# ESP32.net
KiCad netlist of a schematic drawn in Altium Designer
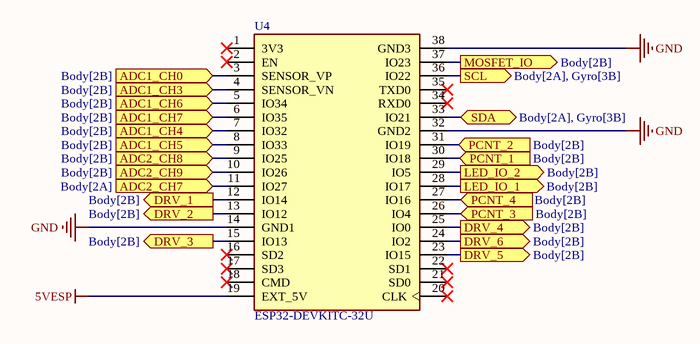
[diagram p0: ESP32.SchDoc]

(export (version "E")
  (design (tool "Eeschema 10.0.6"))
  (components
    (comp (ref "U4")
      (value "ESP32-DEVKITC-32U")
      (footprint "MODULE_ESP32-DEVKITC-32U")
      (fields (field (name "MF") "Espressif Systems"))
      (libsource (lib "MainComponents") (part "ESP32-DEVKITC-32U"))
    )
  )
  (nets
    (net (code "1") (name "/ADC1_CH0") (class "Default")
      (node (ref "U4") (pin "3") (pinfunction "SENSOR_VP_3") (pintype "passive"))
    )
    (net (code "2") (name "/ADC1_CH3") (class "Default")
      (node (ref "U4") (pin "4") (pinfunction "SENSOR_VN_4") (pintype "passive"))
    )
    (net (code "3") (name "/ADC1_CH4") (class "Default")
      (node (ref "U4") (pin "7") (pinfunction "IO32_7") (pintype "passive"))
    )
    (net (code "4") (name "/ADC1_CH5") (class "Default")
      (node (ref "U4") (pin "8") (pinfunction "IO33_8") (pintype "passive"))
    )
    (net (code "5") (name "/ADC1_CH6") (class "Default")
      (node (ref "U4") (pin "5") (pinfunction "IO34_5") (pintype "passive"))
    )
    (net (code "6") (name "/ADC1_CH7") (class "Default")
      (node (ref "U4") (pin "6") (pinfunction "IO35_6") (pintype "passive"))
    )
    (net (code "7") (name "/ADC2_CH7") (class "Default")
      (node (ref "U4") (pin "11") (pinfunction "IO27_11") (pintype "passive"))
    )
    (net (code "8") (name "/ADC2_CH8") (class "Default")
      (node (ref "U4") (pin "9") (pinfunction "IO25_9") (pintype "passive"))
    )
    (net (code "9") (name "/ADC2_CH9") (class "Default")
      (node (ref "U4") (pin "10") (pinfunction "IO26_10") (pintype "passive"))
    )
    (net (code "10") (name "/DRV_1") (class "Default")
      (node (ref "U4") (pin "12") (pinfunction "IO14_12") (pintype "passive"))
    )
    (net (code "11") (name "/DRV_2") (class "Default")
      (node (ref "U4") (pin "13") (pinfunction "IO12_13") (pintype "passive"))
    )
    (net (code "12") (name "/DRV_3") (class "Default")
      (node (ref "U4") (pin "15") (pinfunction "IO13_15") (pintype "passive"))
    )
    (net (code "13") (name "/DRV_4") (class "Default")
      (node (ref "U4") (pin "25") (pinfunction "IO0_25") (pintype "passive"))
    )
    (net (code "14") (name "/DRV_5") (class "Default")
      (node (ref "U4") (pin "23") (pinfunction "IO15_23") (pintype "passive"))
    )
    (net (code "15") (name "/DRV_6") (class "Default")
      (node (ref "U4") (pin "24") (pinfunction "IO2_24") (pintype "passive"))
    )
    (net (code "16") (name "/LED_IO_1") (class "Default")
      (node (ref "U4") (pin "28") (pinfunction "IO17_28") (pintype "passive"))
    )
    (net (code "17") (name "/LED_IO_2") (class "Default")
      (node (ref "U4") (pin "29") (pinfunction "IO5_29") (pintype "passive"))
    )
    (net (code "18") (name "/MOSFET_IO") (class "Default")
      (node (ref "U4") (pin "37") (pinfunction "IO23_37") (pintype "passive"))
    )
    (net (code "19") (name "/PCNT_1") (class "Default")
      (node (ref "U4") (pin "30") (pinfunction "IO18_30") (pintype "passive"))
    )
    (net (code "20") (name "/PCNT_2") (class "Default")
      (node (ref "U4") (pin "31") (pinfunction "IO19_31") (pintype "passive"))
    )
    (net (code "21") (name "/PCNT_3") (class "Default")
      (node (ref "U4") (pin "26") (pinfunction "IO4_26") (pintype "passive"))
    )
    (net (code "22") (name "/PCNT_4") (class "Default")
      (node (ref "U4") (pin "27") (pinfunction "IO16_27") (pintype "passive"))
    )
    (net (code "23") (name "/SCL") (class "Default")
      (node (ref "U4") (pin "36") (pinfunction "IO22_36") (pintype "passive"))
    )
    (net (code "24") (name "/SDA") (class "Default")
      (node (ref "U4") (pin "33") (pinfunction "IO21_33") (pintype "passive"))
    )
    (net (code "25") (name "5VESP") (class "Default")
      (node (ref "U4") (pin "19") (pinfunction "EXT_5V_19") (pintype "passive"))
    )
    (net (code "26") (name "GND") (class "Default")
      (node (ref "U4") (pin "14") (pinfunction "GND1_14") (pintype "passive"))
      (node (ref "U4") (pin "32") (pinfunction "GND2_32") (pintype "passive"))
      (node (ref "U4") (pin "38") (pinfunction "GND3_38") (pintype "passive"))
    )
    (net (code "27") (name "unconnected-(U4-3V3-Pad1)") (class "Default")
      (node (ref "U4") (pin "1") (pinfunction "3V3_1") (pintype "passive+no_connect"))
    )
    (net (code "28") (name "unconnected-(U4-CLK-Pad20)") (class "Default")
      (node (ref "U4") (pin "20") (pinfunction "CLK_20") (pintype "passive+no_connect"))
    )
    (net (code "29") (name "unconnected-(U4-CMD-Pad18)") (class "Default")
      (node (ref "U4") (pin "18") (pinfunction "CMD_18") (pintype "passive+no_connect"))
    )
    (net (code "30") (name "unconnected-(U4-EN-Pad2)") (class "Default")
      (node (ref "U4") (pin "2") (pinfunction "EN_2") (pintype "passive+no_connect"))
    )
    (net (code "31") (name "unconnected-(U4-RXD0-Pad34)") (class "Default")
      (node (ref "U4") (pin "34") (pinfunction "RXD0_34") (pintype "passive+no_connect"))
    )
    (net (code "32") (name "unconnected-(U4-SD0-Pad21)") (class "Default")
      (node (ref "U4") (pin "21") (pinfunction "SD0_21") (pintype "passive+no_connect"))
    )
    (net (code "33") (name "unconnected-(U4-SD1-Pad22)") (class "Default")
      (node (ref "U4") (pin "22") (pinfunction "SD1_22") (pintype "passive+no_connect"))
    )
    (net (code "34") (name "unconnected-(U4-SD2-Pad16)") (class "Default")
      (node (ref "U4") (pin "16") (pinfunction "SD2_16") (pintype "passive+no_connect"))
    )
    (net (code "35") (name "unconnected-(U4-SD3-Pad17)") (class "Default")
      (node (ref "U4") (pin "17") (pinfunction "SD3_17") (pintype "passive+no_connect"))
    )
    (net (code "36") (name "unconnected-(U4-TXD0-Pad35)") (class "Default")
      (node (ref "U4") (pin "35") (pinfunction "TXD0_35") (pintype "passive+no_connect"))
    )
  )
)
